# Dust1_MotherBoard_PWR.net
KiCad netlist of a schematic drawn in Altium Designer
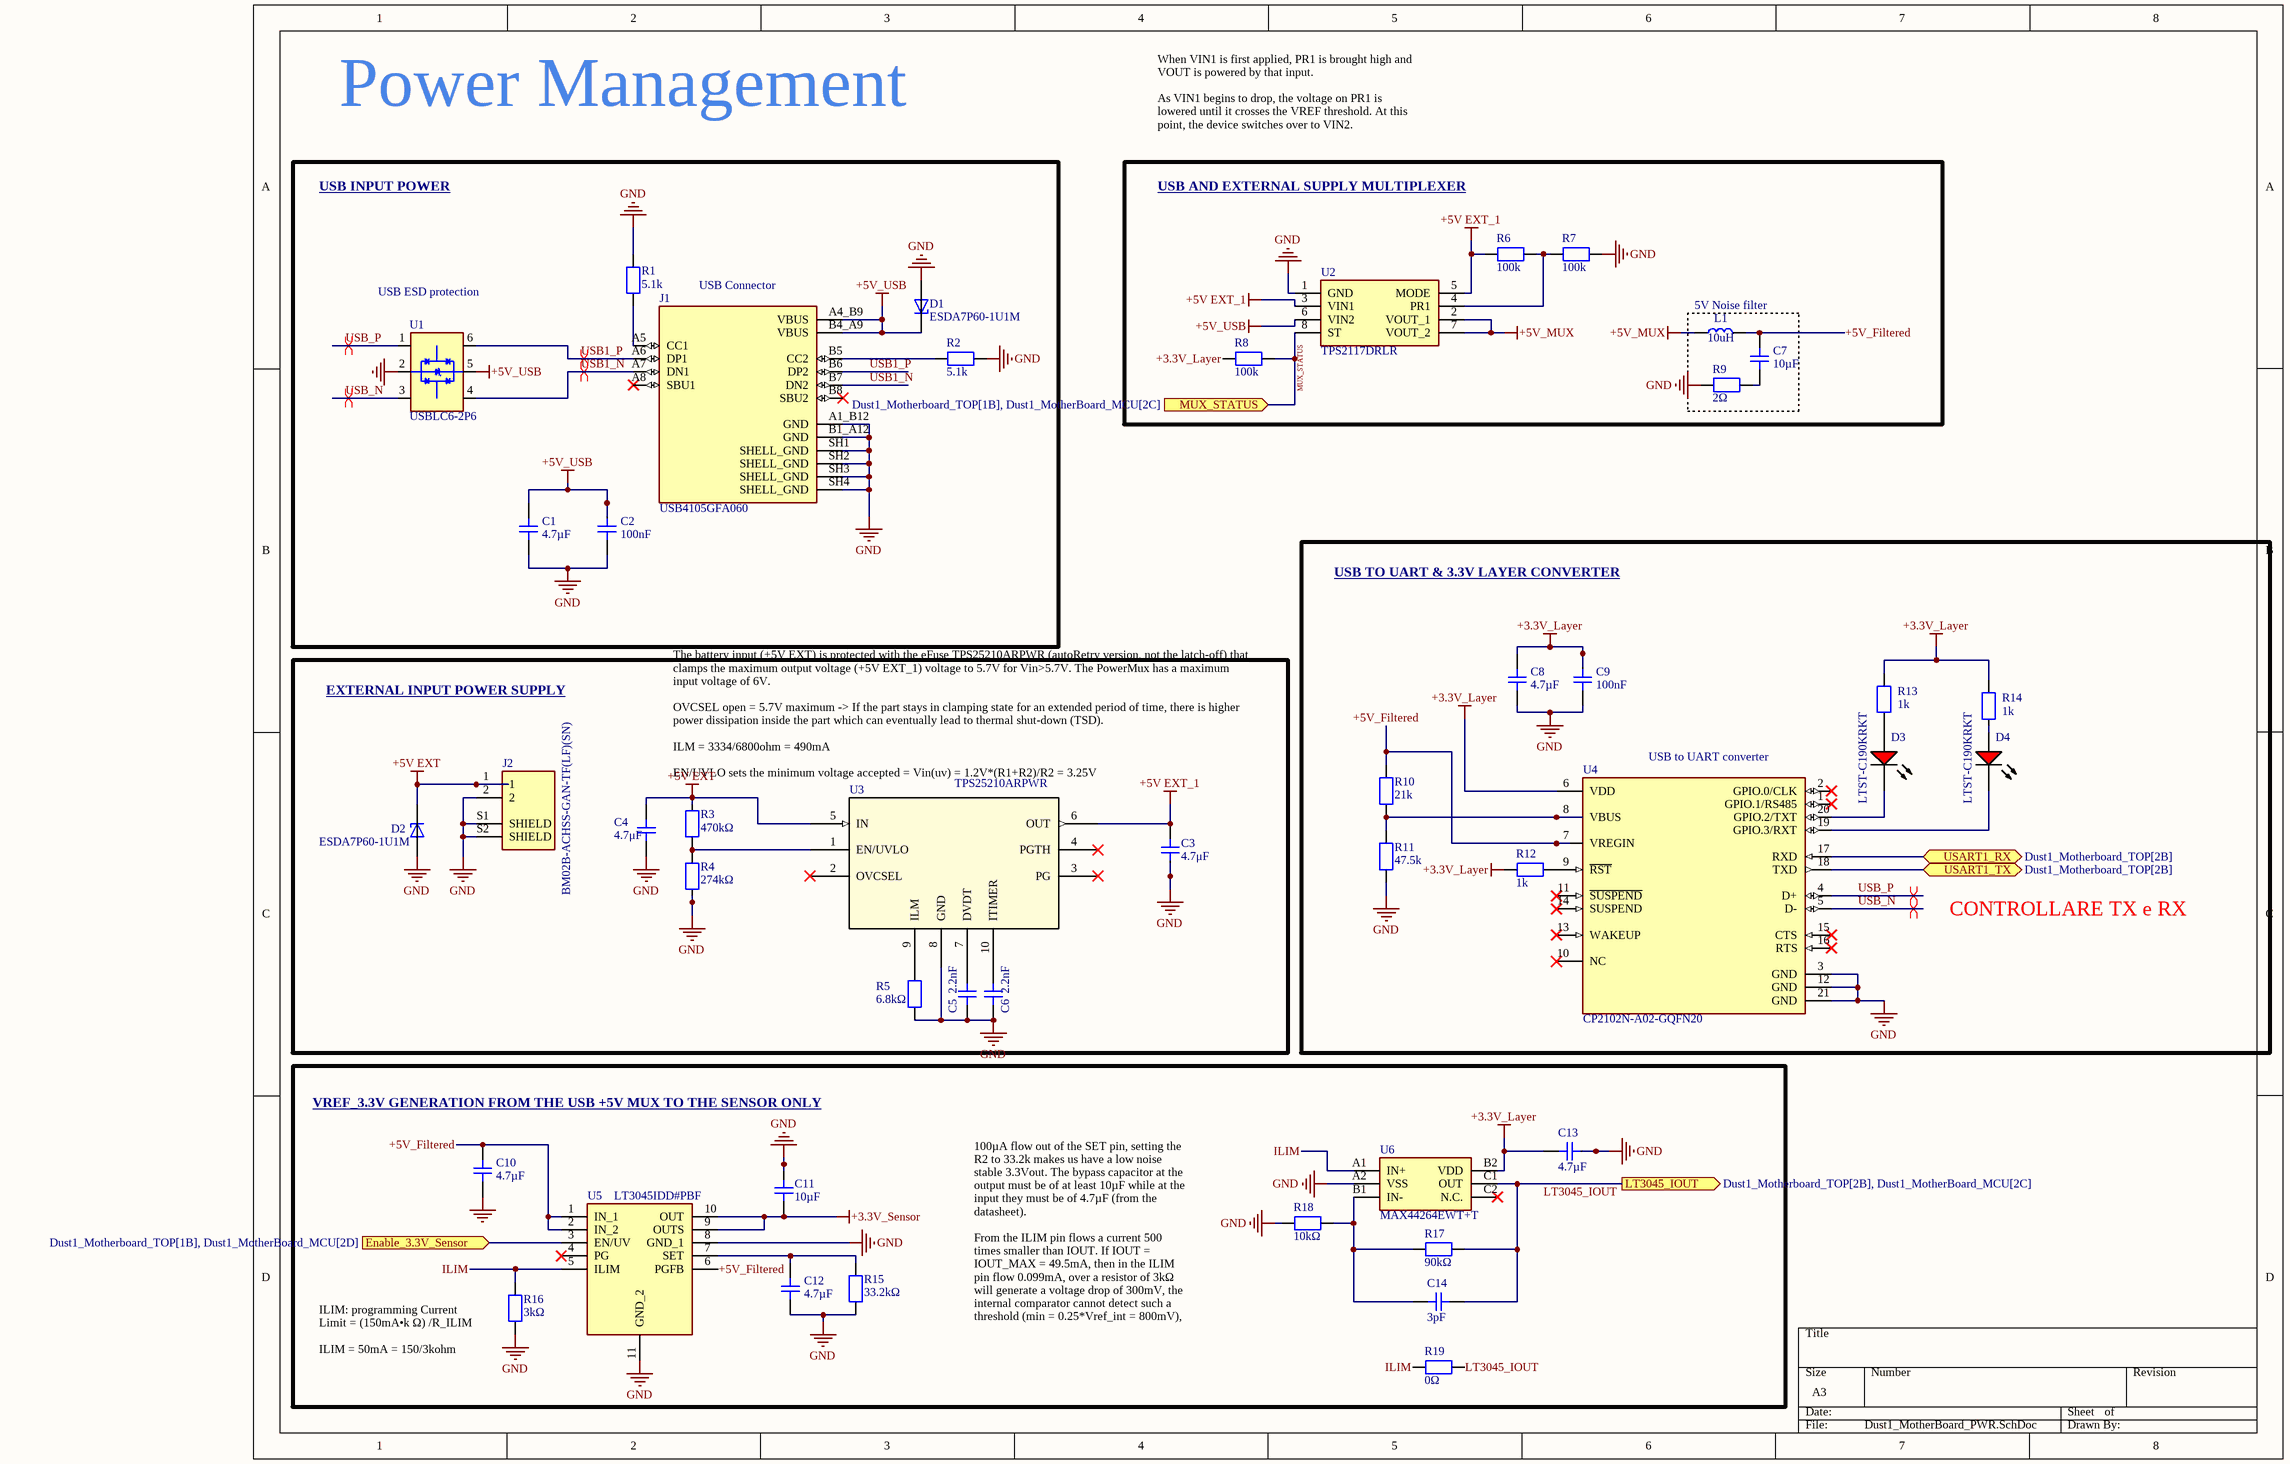
[diagram p0: Dust1_MotherBoard_PWR.SchDoc]

(export (version "E")
  (design (tool "Eeschema 10.0.6"))
  (components
    (comp (ref "C1")
      (value "4.7µF")
      (footprint "CAP_0603")
      (libsource (lib "I3N - LABSAMP") (part "CAP_0603"))
    )
    (comp (ref "C2")
      (value "100nF")
      (footprint "CAP_0603")
      (libsource (lib "I3N - LABSAMP") (part "CAP_0603"))
    )
    (comp (ref "C3")
      (value "4.7μF")
      (footprint "CAP_0603")
      (libsource (lib "I3N - LABSAMP") (part "CAP_0603"))
    )
    (comp (ref "C4")
      (value "4.7μF")
      (footprint "CAP_0603")
      (libsource (lib "I3N - LABSAMP") (part "CAP_0603"))
    )
    (comp (ref "C5")
      (value "2.2nF")
      (footprint "CAP_0402")
      (description "Generic 0402 Capacitor")
      (libsource (lib "I3N - LABSAMP") (part "CAP_0402"))
    )
    (comp (ref "C6")
      (value "2.2nF")
      (footprint "CAP_0402")
      (description "Generic 0402 Capacitor")
      (libsource (lib "I3N - LABSAMP") (part "CAP_0402"))
    )
    (comp (ref "C7")
      (value "10µF")
      (footprint "CAP_0603")
      (libsource (lib "I3N - LABSAMP") (part "CAP_0603"))
    )
    (comp (ref "C8")
      (value "4.7µF")
      (footprint "CAP_0603")
      (libsource (lib "I3N - LABSAMP") (part "CAP_0603"))
    )
    (comp (ref "C9")
      (value "100nF")
      (footprint "CAP_0603")
      (libsource (lib "I3N - LABSAMP") (part "CAP_0603"))
    )
    (comp (ref "C10")
      (value "4.7µF")
      (footprint "CAP_0603")
      (libsource (lib "I3N - LABSAMP") (part "CAP_0603"))
    )
    (comp (ref "C11")
      (value "10µF")
      (footprint "CAP_0603")
      (libsource (lib "I3N - LABSAMP") (part "CAP_0603"))
    )
    (comp (ref "C12")
      (value "4.7µF")
      (footprint "CAP_0603")
      (libsource (lib "I3N - LABSAMP") (part "CAP_0603"))
    )
    (comp (ref "C13")
      (value "4.7µF")
      (footprint "CAP_0603")
      (libsource (lib "I3N - LABSAMP") (part "CAP_0603"))
    )
    (comp (ref "C14")
      (value "3pF")
      (footprint "CAP_0402")
      (description "Generic 0402 Capacitor")
      (libsource (lib "I3N - LABSAMP") (part "CAP_0402"))
    )
    (comp (ref "D1")
      (value "ESDA7P60-1U1M")
      (footprint "TVS_ESDA7P60-1U1M")
      (fields (field (name "MF") "{'manufacturer': u'STMicroelectronics'}"))
      (libsource (lib "I3N - LABSAMP") (part "ESDA7P60-1U1M"))
    )
    (comp (ref "D2")
      (value "ESDA7P60-1U1M")
      (footprint "TVS_ESDA7P60-1U1M")
      (fields (field (name "MF") "{'manufacturer': u'STMicroelectronics'}"))
      (libsource (lib "I3N - LABSAMP") (part "ESDA7P60-1U1M"))
    )
    (comp (ref "D3")
      (value "LTST-C190KRKT")
      (footprint "LTST-C191KRKT_V")
      (description "LED Uni-Color Red, 62.5 mW, 25 mA, -30 to 85 degC, 2-Pin SMD, RoHS, Tape and Reel")
      (fields (field (name "POWER") "75mW") (field (name "MANUFACTURER") "Lite-On"))
      (libsource (lib "I3N - LABSAMP") (part "LED-RED-AK-2"))
    )
    (comp (ref "D4")
      (value "LTST-C190KRKT")
      (footprint "LTST-C191KRKT_V")
      (description "LED Uni-Color Red, 62.5 mW, 25 mA, -30 to 85 degC, 2-Pin SMD, RoHS, Tape and Reel")
      (fields (field (name "POWER") "75mW") (field (name "MANUFACTURER") "Lite-On"))
      (libsource (lib "I3N - LABSAMP") (part "LED-RED-AK-2"))
    )
    (comp (ref "J1")
      (value "USB4105GFA060")
      (footprint "GCT_USB4105GFA060")
      (fields (field (name "MF") "Global Connector Technology"))
      (libsource (lib "I3N - LABSAMP") (part "USB4105GFA060"))
    )
    (comp (ref "J2")
      (value "BM02B-ACHSS-GAN-TF(LF)(SN)")
      (footprint "JST_BM02B-ACHSS-GAN-TF(LF)(SN)")
      (description "Connector Header Surface Mount, Right Angle 2 position 0.047 (1.20mm)")
      (fields (field (name "MF") "JST Sales"))
      (libsource (lib "I3N - LABSAMP") (part "BM02B-ACHSS-GAN-TF(LF)(SN)"))
    )
    (comp (ref "L1")
      (value "10uH")
      (footprint "IND_0603")
      (description "Generic 0603 Inductor")
      (libsource (lib "I3N - LABSAMP") (part "IND_0603"))
    )
    (comp (ref "R1")
      (value "5.1k")
      (footprint "RES_0603")
      (libsource (lib "I3N - LABSAMP") (part "RES_0603"))
    )
    (comp (ref "R2")
      (value "5.1k")
      (footprint "RES_0603")
      (libsource (lib "I3N - LABSAMP") (part "RES_0603"))
    )
    (comp (ref "R3")
      (value "470kΩ")
      (footprint "RES_0603")
      (libsource (lib "I3N - LABSAMP") (part "RES_0603"))
    )
    (comp (ref "R4")
      (value "274kΩ")
      (footprint "RES_0603")
      (libsource (lib "I3N - LABSAMP") (part "RES_0603"))
    )
    (comp (ref "R5")
      (value "6.8kΩ")
      (footprint "RES_0603")
      (libsource (lib "I3N - LABSAMP") (part "RES_0603"))
    )
    (comp (ref "R6")
      (value "100k")
      (footprint "RES_0402")
      (description "Resistor SMD 0402 Generic")
      (libsource (lib "I3N - LABSAMP") (part "RES_0402"))
    )
    (comp (ref "R7")
      (value "100k")
      (footprint "RES_0402")
      (description "Resistor SMD 0402 Generic")
      (libsource (lib "I3N - LABSAMP") (part "RES_0402"))
    )
    (comp (ref "R8")
      (value "100k")
      (footprint "RES_0402")
      (description "Resistor SMD 0402 Generic")
      (libsource (lib "I3N - LABSAMP") (part "RES_0402"))
    )
    (comp (ref "R9") (value "2Ω") (footprint "RES_0603") (libsource (lib "I3N - LABSAMP") (part "RES_0603")))
    (comp (ref "R10")
      (value "21k")
      (footprint "RES_0603")
      (libsource (lib "I3N - LABSAMP") (part "RES_0603"))
    )
    (comp (ref "R11")
      (value "47.5k")
      (footprint "RES_0603")
      (libsource (lib "I3N - LABSAMP") (part "RES_0603"))
    )
    (comp (ref "R12")
      (value "1k")
      (footprint "RES_0402")
      (description "Resistor SMD 0402 Generic")
      (libsource (lib "I3N - LABSAMP") (part "RES_0402"))
    )
    (comp (ref "R13")
      (value "1k")
      (footprint "RES_0402")
      (description "Resistor SMD 0402 Generic")
      (libsource (lib "I3N - LABSAMP") (part "RES_0402"))
    )
    (comp (ref "R14")
      (value "1k")
      (footprint "RES_0402")
      (description "Resistor SMD 0402 Generic")
      (libsource (lib "I3N - LABSAMP") (part "RES_0402"))
    )
    (comp (ref "R15")
      (value "33.2kΩ")
      (footprint "RES_0402")
      (description "Resistor SMD 0402 Generic")
      (libsource (lib "I3N - LABSAMP") (part "RES_0402"))
    )
    (comp (ref "R16")
      (value "3kΩ")
      (footprint "RES_0402")
      (description "Resistor SMD 0402 Generic")
      (libsource (lib "I3N - LABSAMP") (part "RES_0402"))
    )
    (comp (ref "R17")
      (value "90kΩ")
      (footprint "RES_0402")
      (description "Resistor SMD 0402 Generic")
      (libsource (lib "I3N - LABSAMP") (part "RES_0402"))
    )
    (comp (ref "R18")
      (value "10kΩ")
      (footprint "RES_0402")
      (description "Resistor SMD 0402 Generic")
      (libsource (lib "I3N - LABSAMP") (part "RES_0402"))
    )
    (comp (ref "R19") (value "0Ω") (footprint "RES_0603") (libsource (lib "I3N - LABSAMP") (part "RES_0603")))
    (comp (ref "U1")
      (value "USBLC6-2P6")
      (footprint "SOT50P160X60-6N")
      (description "17V Clamp 5A (8/20Âµs) Ipp Tvs Diode Surface Mount SOT-666")
      (fields (field (name "MF") "STMicroelectronics"))
      (libsource (lib "I3N - LABSAMP") (part "USBLC6-2P6"))
    )
    (comp (ref "U2")
      (value "TPS2117DRLR")
      (footprint "SOTFL50P160X60-8N")
      (fields (field (name "MOUSER PART NUMBER") "595-TPS2117DRLR"))
      (libsource (lib "I3N - LABSAMP") (part "TPS2117DRLR"))
    )
    (comp (ref "U3")
      (value "TPS25210ARPWR")
      (footprint "TPS259460ARPWR_TEX")
      (description "2.7-V to 5.7-V, 31-mâ„")
      (fields (field (name "COPYRIGHT") "Copyright (C) 2025 Ultra Librarian. All rights reserved."))
      (libsource (lib "I3N - LABSAMP") (part "TPS25210ARPWR"))
    )
    (comp (ref "U4")
      (value "CP2102N-A02-GQFN20")
      (footprint "FP-CP2102N-A02-GQFN20-MFG")
      (description "IC USB TO UART BRIDGE QFN20")
      (libsource (lib "Altium Content Vault") (part "535e9eb0fa6e07ebb008498c6833ade"))
    )
    (comp (ref "U5")
      (value "LT3045IDD#PBF")
      (footprint "SON50P300X300X80-11N-D")
      (description "Linear Technology LT3045IDD#PBF, LDO Regulator, 500mA Adjustable, 0  15 V, +/-1% 10-Pin, DFN")
      (fields (field (name "MOUSER PART NUMBER") "584-LT3045IDD#PBF"))
      (libsource (lib "I3N - LABSAMP") (part "LT3045IDD#PBF"))
    )
    (comp (ref "U6")
      (value "MAX44264EWT+T")
      (footprint "BGA6C40P2X3_91X131X69")
      (fields (field (name "MOUSER PART NUMBER") "700-MAX44264EWT+T"))
      (libsource (lib "I3N - LABSAMP") (part "MAX44264EWT+T"))
    )
  )
  (nets
    (net (code "1") (name "+3.3V_Layer") (class "Default")
      (node (ref "C13") (pin "2") (pintype "passive"))
      (node (ref "C8") (pin "2") (pintype "passive"))
      (node (ref "C9") (pin "2") (pintype "passive"))
      (node (ref "R12") (pin "2") (pintype "passive"))
      (node (ref "R13") (pin "2") (pintype "passive"))
      (node (ref "R14") (pin "2") (pintype "passive"))
      (node (ref "R8") (pin "2") (pintype "passive"))
      (node (ref "U4") (pin "6") (pinfunction "VDD_6") (pintype "power_in"))
      (node (ref "U6") (pin "B2") (pinfunction "VDD_B2") (pintype "passive"))
    )
    (net (code "2") (name "+3.3V_Sensor") (class "Default")
      (node (ref "C11") (pin "1") (pintype "passive"))
      (node (ref "U5") (pin "10") (pinfunction "OUT_10") (pintype "passive"))
      (node (ref "U5") (pin "9") (pinfunction "OUTS_9") (pintype "passive"))
    )
    (net (code "3") (name "+5V EXT") (class "Default")
      (node (ref "C4") (pin "2") (pintype "passive"))
      (node (ref "D2") (pin "1") (pinfunction "1_1") (pintype "passive"))
      (node (ref "J2") (pin "1") (pinfunction "1_1") (pintype "passive"))
      (node (ref "R3") (pin "1") (pintype "passive"))
      (node (ref "U3") (pin "5") (pinfunction "IN_5") (pintype "input"))
    )
    (net (code "4") (name "+5V EXT_1") (class "Default")
      (node (ref "C3") (pin "2") (pintype "passive"))
      (node (ref "R6") (pin "1") (pintype "passive"))
      (node (ref "U2") (pin "3") (pinfunction "VIN1_3") (pintype "passive"))
      (node (ref "U2") (pin "5") (pinfunction "MODE_5") (pintype "passive"))
      (node (ref "U3") (pin "6") (pinfunction "OUT_6") (pintype "output"))
    )
    (net (code "5") (name "+5V_MUX") (class "Default")
      (node (ref "L1") (pin "1") (pintype "passive"))
      (node (ref "U2") (pin "2") (pinfunction "VOUT_1_2") (pintype "passive"))
      (node (ref "U2") (pin "7") (pinfunction "VOUT_2_7") (pintype "passive"))
    )
    (net (code "6") (name "+5V_USB") (class "Default")
      (node (ref "C1") (pin "2") (pintype "passive"))
      (node (ref "C2") (pin "2") (pintype "passive"))
      (node (ref "D1") (pin "1") (pinfunction "1_1") (pintype "passive"))
      (node (ref "J1") (pin "A4_B9") (pinfunction "VBUS_A4_B9") (pintype "power_in"))
      (node (ref "J1") (pin "B4_A9") (pinfunction "VBUS_B4_A9") (pintype "power_in"))
      (node (ref "U1") (pin "5") (pinfunction "VBUS_5") (pintype "power_in"))
      (node (ref "U2") (pin "6") (pinfunction "VIN2_6") (pintype "passive"))
    )
    (net (code "7") (name "/+5V_Filtered") (class "Default")
      (node (ref "C10") (pin "2") (pintype "passive"))
      (node (ref "C7") (pin "2") (pintype "passive"))
      (node (ref "L1") (pin "2") (pintype "passive"))
      (node (ref "R10") (pin "1") (pintype "passive"))
      (node (ref "U4") (pin "7") (pinfunction "VREGIN_7") (pintype "power_in"))
      (node (ref "U5") (pin "1") (pinfunction "IN_1_1") (pintype "passive"))
      (node (ref "U5") (pin "2") (pinfunction "IN_2_2") (pintype "passive"))
      (node (ref "U5") (pin "6") (pinfunction "PGFB_6") (pintype "passive"))
    )
    (net (code "8") (name "/Enable_3.3V_Sensor") (class "Default")
      (node (ref "U5") (pin "3") (pinfunction "EN/UV_3") (pintype "passive"))
    )
    (net (code "9") (name "/ILIM") (class "Default")
      (node (ref "R16") (pin "1") (pintype "passive"))
      (node (ref "R19") (pin "1") (pintype "passive"))
      (node (ref "U5") (pin "5") (pinfunction "ILIM_5") (pintype "passive"))
      (node (ref "U6") (pin "A1") (pinfunction "IN+_A1") (pintype "passive"))
    )
    (net (code "10") (name "/LT3045_IOUT") (class "Default")
      (node (ref "C14") (pin "2") (pintype "passive"))
      (node (ref "R17") (pin "1") (pintype "passive"))
      (node (ref "R19") (pin "2") (pintype "passive"))
      (node (ref "U6") (pin "C1") (pinfunction "OUT_C1") (pintype "passive"))
    )
    (net (code "11") (name "/MUX_STATUS") (class "Default")
      (node (ref "R8") (pin "1") (pintype "passive"))
      (node (ref "U2") (pin "8") (pinfunction "ST_8") (pintype "passive"))
    )
    (net (code "12") (name "/USART1_RX") (class "Default")
      (node (ref "U4") (pin "17") (pinfunction "RXD_17") (pintype "input"))
    )
    (net (code "13") (name "/USART1_TX") (class "Default")
      (node (ref "U4") (pin "18") (pinfunction "TXD_18") (pintype "output"))
    )
    (net (code "14") (name "/USB1_N") (class "Default")
      (node (ref "J1") (pin "A7") (pinfunction "DN1_A7") (pintype "bidirectional"))
      (node (ref "J1") (pin "B7") (pinfunction "DN2_B7") (pintype "bidirectional"))
      (node (ref "U1") (pin "4") (pinfunction "I/O2_2_4") (pintype "bidirectional"))
    )
    (net (code "15") (name "/USB1_P") (class "Default")
      (node (ref "J1") (pin "A6") (pinfunction "DP1_A6") (pintype "bidirectional"))
      (node (ref "J1") (pin "B6") (pinfunction "DP2_B6") (pintype "bidirectional"))
      (node (ref "U1") (pin "6") (pinfunction "I/O1_2_6") (pintype "bidirectional"))
    )
    (net (code "16") (name "/USB_N") (class "Default")
      (node (ref "U1") (pin "3") (pinfunction "I/O2_1_3") (pintype "bidirectional"))
      (node (ref "U4") (pin "5") (pinfunction "D-_5") (pintype "bidirectional"))
    )
    (net (code "17") (name "/USB_P") (class "Default")
      (node (ref "U1") (pin "1") (pinfunction "I/O1_1_1") (pintype "bidirectional"))
      (node (ref "U4") (pin "4") (pinfunction "D+_4") (pintype "bidirectional"))
    )
    (net (code "18") (name "GND") (class "Default")
      (node (ref "C1") (pin "1") (pintype "passive"))
      (node (ref "C10") (pin "1") (pintype "passive"))
      (node (ref "C11") (pin "2") (pintype "passive"))
      (node (ref "C12") (pin "1") (pintype "passive"))
      (node (ref "C13") (pin "1") (pintype "passive"))
      (node (ref "C2") (pin "1") (pintype "passive"))
      (node (ref "C3") (pin "1") (pintype "passive"))
      (node (ref "C4") (pin "1") (pintype "passive"))
      (node (ref "C5") (pin "2") (pintype "passive"))
      (node (ref "C6") (pin "2") (pintype "passive"))
      (node (ref "C8") (pin "1") (pintype "passive"))
      (node (ref "C9") (pin "1") (pintype "passive"))
      (node (ref "D1") (pin "2") (pinfunction "2_2") (pintype "passive"))
      (node (ref "D2") (pin "2") (pinfunction "2_2") (pintype "passive"))
      (node (ref "J1") (pin "A1_B12") (pinfunction "GND_A1_B12") (pintype "power_in"))
      (node (ref "J1") (pin "B1_A12") (pinfunction "GND_B1_A12") (pintype "power_in"))
      (node (ref "J1") (pin "SH1") (pinfunction "SHELL_GND_SH1") (pintype "power_in"))
      (node (ref "J1") (pin "SH2") (pinfunction "SHELL_GND_SH2") (pintype "power_in"))
      (node (ref "J1") (pin "SH3") (pinfunction "SHELL_GND_SH3") (pintype "power_in"))
      (node (ref "J1") (pin "SH4") (pinfunction "SHELL_GND_SH4") (pintype "power_in"))
      (node (ref "J2") (pin "2") (pinfunction "2_2") (pintype "passive"))
      (node (ref "J2") (pin "S1") (pinfunction "SHIELD_S1") (pintype "passive"))
      (node (ref "J2") (pin "S2") (pinfunction "SHIELD_S2") (pintype "passive"))
      (node (ref "R1") (pin "2") (pintype "passive"))
      (node (ref "R11") (pin "2") (pintype "passive"))
      (node (ref "R15") (pin "2") (pintype "passive"))
      (node (ref "R16") (pin "2") (pintype "passive"))
      (node (ref "R18") (pin "2") (pintype "passive"))
      (node (ref "R2") (pin "1") (pintype "passive"))
      (node (ref "R4") (pin "2") (pintype "passive"))
      (node (ref "R5") (pin "2") (pintype "passive"))
      (node (ref "R7") (pin "2") (pintype "passive"))
      (node (ref "R9") (pin "1") (pintype "passive"))
      (node (ref "U1") (pin "2") (pinfunction "GND_2") (pintype "power_in"))
      (node (ref "U2") (pin "1") (pinfunction "GND_1") (pintype "passive"))
      (node (ref "U3") (pin "8") (pinfunction "GND_8") (pintype "power_in"))
      (node (ref "U4") (pin "12") (pinfunction "GND_12") (pintype "power_in"))
      (node (ref "U4") (pin "21") (pinfunction "GND_21") (pintype "power_in"))
      (node (ref "U4") (pin "3") (pinfunction "GND_3") (pintype "power_in"))
      (node (ref "U5") (pin "11") (pinfunction "GND_2_11") (pintype "passive"))
      (node (ref "U5") (pin "8") (pinfunction "GND_1_8") (pintype "passive"))
      (node (ref "U6") (pin "A2") (pinfunction "VSS_A2") (pintype "passive"))
    )
    (net (code "19") (name "Net-(C7-Pad1)") (class "Default")
      (node (ref "C7") (pin "1") (pintype "passive"))
      (node (ref "R9") (pin "2") (pintype "passive"))
    )
    (net (code "20") (name "Net-(D3-A)") (class "Default")
      (node (ref "D3") (pin "1") (pinfunction "A_1") (pintype "passive"))
      (node (ref "R13") (pin "1") (pintype "passive"))
    )
    (net (code "21") (name "Net-(D3-K)") (class "Default")
      (node (ref "D3") (pin "2") (pinfunction "K_2") (pintype "passive"))
      (node (ref "U4") (pin "20") (pinfunction "GPIO.2/TXT_20") (pintype "bidirectional"))
    )
    (net (code "22") (name "Net-(D4-A)") (class "Default")
      (node (ref "D4") (pin "1") (pinfunction "A_1") (pintype "passive"))
      (node (ref "R14") (pin "1") (pintype "passive"))
    )
    (net (code "23") (name "Net-(D4-K)") (class "Default")
      (node (ref "D4") (pin "2") (pinfunction "K_2") (pintype "passive"))
      (node (ref "U4") (pin "19") (pinfunction "GPIO.3/RXT_19") (pintype "bidirectional"))
    )
    (net (code "24") (name "Net-(J1-CC1)") (class "Default")
      (node (ref "J1") (pin "A5") (pinfunction "CC1_A5") (pintype "bidirectional"))
      (node (ref "R1") (pin "1") (pintype "passive"))
    )
    (net (code "25") (name "Net-(J1-CC2)") (class "Default")
      (node (ref "J1") (pin "B5") (pinfunction "CC2_B5") (pintype "bidirectional"))
      (node (ref "R2") (pin "2") (pintype "passive"))
    )
    (net (code "26") (name "Net-(U2-PR1)") (class "Default")
      (node (ref "R6") (pin "2") (pintype "passive"))
      (node (ref "R7") (pin "1") (pintype "passive"))
      (node (ref "U2") (pin "4") (pinfunction "PR1_4") (pintype "passive"))
    )
    (net (code "27") (name "Net-(U3-DVDT)") (class "Default")
      (node (ref "C5") (pin "1") (pintype "passive"))
      (node (ref "U3") (pin "7") (pinfunction "DVDT_7") (pintype "passive"))
    )
    (net (code "28") (name "Net-(U3-EN{slash}UVLO)") (class "Default")
      (node (ref "R3") (pin "2") (pintype "passive"))
      (node (ref "R4") (pin "1") (pintype "passive"))
      (node (ref "U3") (pin "1") (pinfunction "EN/UVLO_1") (pintype "passive"))
    )
    (net (code "29") (name "Net-(U3-ILM)") (class "Default")
      (node (ref "R5") (pin "1") (pintype "passive"))
      (node (ref "U3") (pin "9") (pinfunction "ILM_9") (pintype "passive"))
    )
    (net (code "30") (name "Net-(U3-ITIMER)") (class "Default")
      (node (ref "C6") (pin "1") (pintype "passive"))
      (node (ref "U3") (pin "10") (pinfunction "ITIMER_10") (pintype "passive"))
    )
    (net (code "31") (name "Net-(U4-VBUS)") (class "Default")
      (node (ref "R10") (pin "2") (pintype "passive"))
      (node (ref "R11") (pin "1") (pintype "passive"))
      (node (ref "U4") (pin "8") (pinfunction "VBUS_8") (pintype "power_in"))
    )
    (net (code "32") (name "Net-(U4-~{RST})") (class "Default")
      (node (ref "R12") (pin "1") (pintype "passive"))
      (node (ref "U4") (pin "9") (pinfunction "~{RST}_9") (pintype "input"))
    )
    (net (code "33") (name "Net-(U5-SET)") (class "Default")
      (node (ref "C12") (pin "2") (pintype "passive"))
      (node (ref "R15") (pin "1") (pintype "passive"))
      (node (ref "U5") (pin "7") (pinfunction "SET_7") (pintype "passive"))
    )
    (net (code "34") (name "Net-(U6-IN-)") (class "Default")
      (node (ref "C14") (pin "1") (pintype "passive"))
      (node (ref "R17") (pin "2") (pintype "passive"))
      (node (ref "R18") (pin "1") (pintype "passive"))
      (node (ref "U6") (pin "B1") (pinfunction "IN-_B1") (pintype "passive"))
    )
    (net (code "35") (name "unconnected-(J1-SBU1-PadA8)") (class "Default")
      (node (ref "J1") (pin "A8") (pinfunction "SBU1_A8") (pintype "bidirectional+no_connect"))
    )
    (net (code "36") (name "unconnected-(J1-SBU2-PadB8)") (class "Default")
      (node (ref "J1") (pin "B8") (pinfunction "SBU2_B8") (pintype "bidirectional+no_connect"))
    )
    (net (code "37") (name "unconnected-(U3-OVCSEL-Pad2)") (class "Default")
      (node (ref "U3") (pin "2") (pinfunction "OVCSEL_2") (pintype "passive+no_connect"))
    )
    (net (code "38") (name "unconnected-(U3-PG-Pad3)") (class "Default")
      (node (ref "U3") (pin "3") (pinfunction "PG_3") (pintype "passive+no_connect"))
    )
    (net (code "39") (name "unconnected-(U3-PGTH-Pad4)") (class "Default")
      (node (ref "U3") (pin "4") (pinfunction "PGTH_4") (pintype "passive+no_connect"))
    )
    (net (code "40") (name "unconnected-(U4-CTS-Pad15)") (class "Default")
      (node (ref "U4") (pin "15") (pinfunction "CTS_15") (pintype "input+no_connect"))
    )
    (net (code "41") (name "unconnected-(U4-GPIO.0{slash}CLK-Pad2)") (class "Default")
      (node (ref "U4") (pin "2") (pinfunction "GPIO.0/CLK_2") (pintype "bidirectional+no_connect"))
    )
    (net (code "42") (name "unconnected-(U4-GPIO.1{slash}RS485-Pad1)") (class "Default")
      (node (ref "U4") (pin "1") (pinfunction "GPIO.1/RS485_1") (pintype "bidirectional+no_connect"))
    )
    (net (code "43") (name "unconnected-(U4-NC-Pad10)") (class "Default")
      (node (ref "U4") (pin "10") (pinfunction "NC_10") (pintype "passive+no_connect"))
    )
    (net (code "44") (name "unconnected-(U4-RTS-Pad16)") (class "Default")
      (node (ref "U4") (pin "16") (pinfunction "RTS_16") (pintype "input+no_connect"))
    )
    (net (code "45") (name "unconnected-(U4-SUSPEND-Pad14)") (class "Default")
      (node (ref "U4") (pin "14") (pinfunction "SUSPEND_14") (pintype "input+no_connect"))
    )
    (net (code "46") (name "unconnected-(U4-WAKEUP-Pad13)") (class "Default")
      (node (ref "U4") (pin "13") (pinfunction "WAKEUP_13") (pintype "input+no_connect"))
    )
    (net (code "47") (name "unconnected-(U4-~{SUSPEND}-Pad11)") (class "Default")
      (node (ref "U4") (pin "11") (pinfunction "~{SUSPEND}_11") (pintype "input+no_connect"))
    )
    (net (code "48") (name "unconnected-(U5-PG-Pad4)") (class "Default")
      (node (ref "U5") (pin "4") (pinfunction "PG_4") (pintype "passive+no_connect"))
    )
    (net (code "49") (name "unconnected-(U6-N.C.-PadC2)") (class "Default")
      (node (ref "U6") (pin "C2") (pinfunction "N.C._C2") (pintype "passive+no_connect"))
    )
  )
)
